# EPS.net
KiCad netlist of a schematic drawn in EAGLE
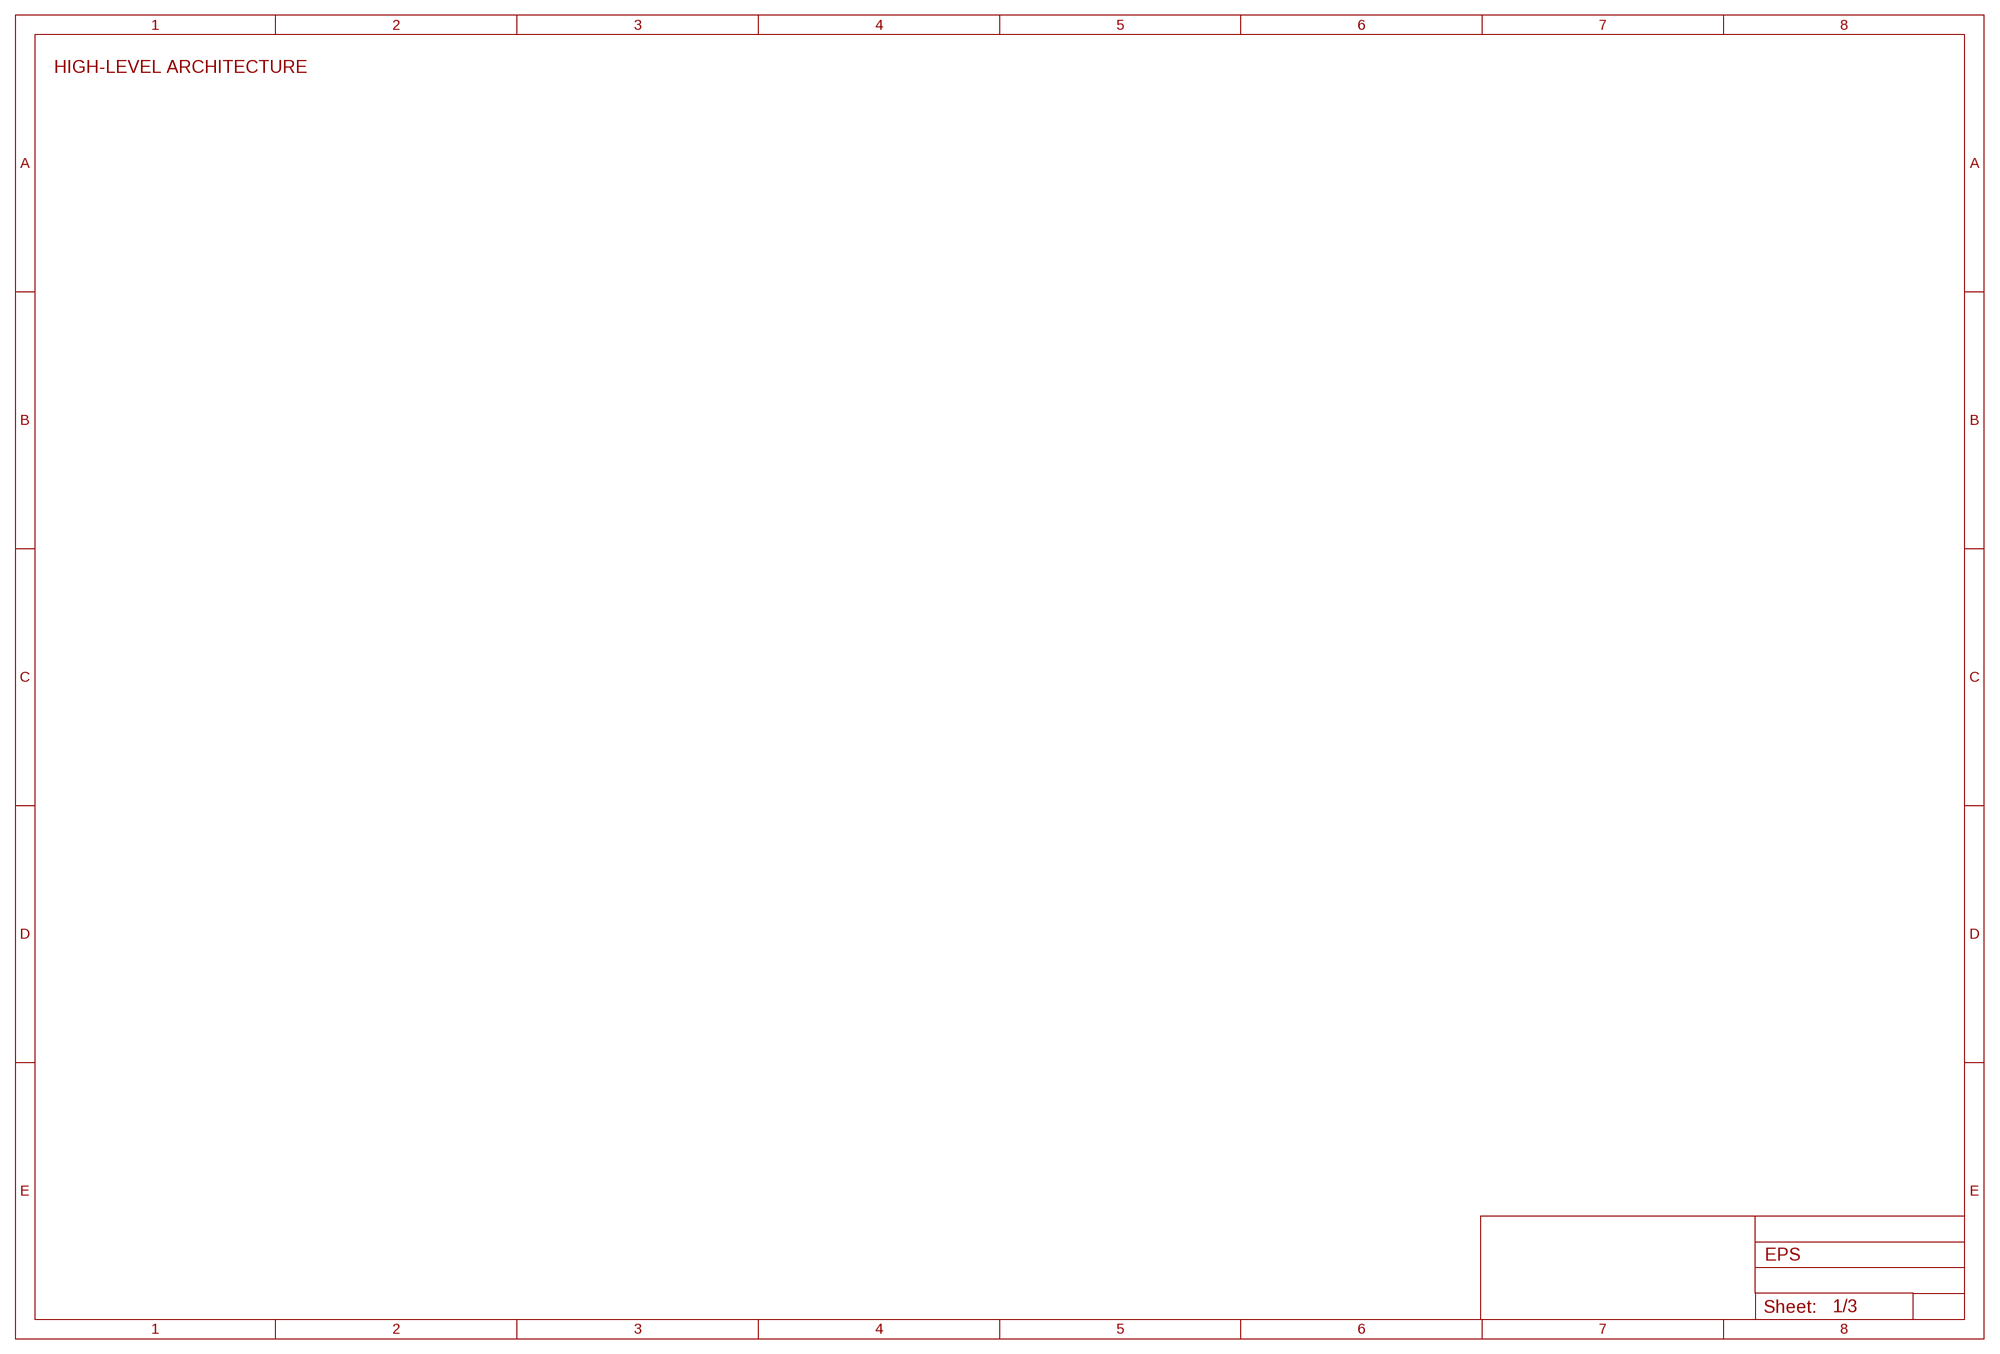
[diagram p0: schematic, sheet 1]
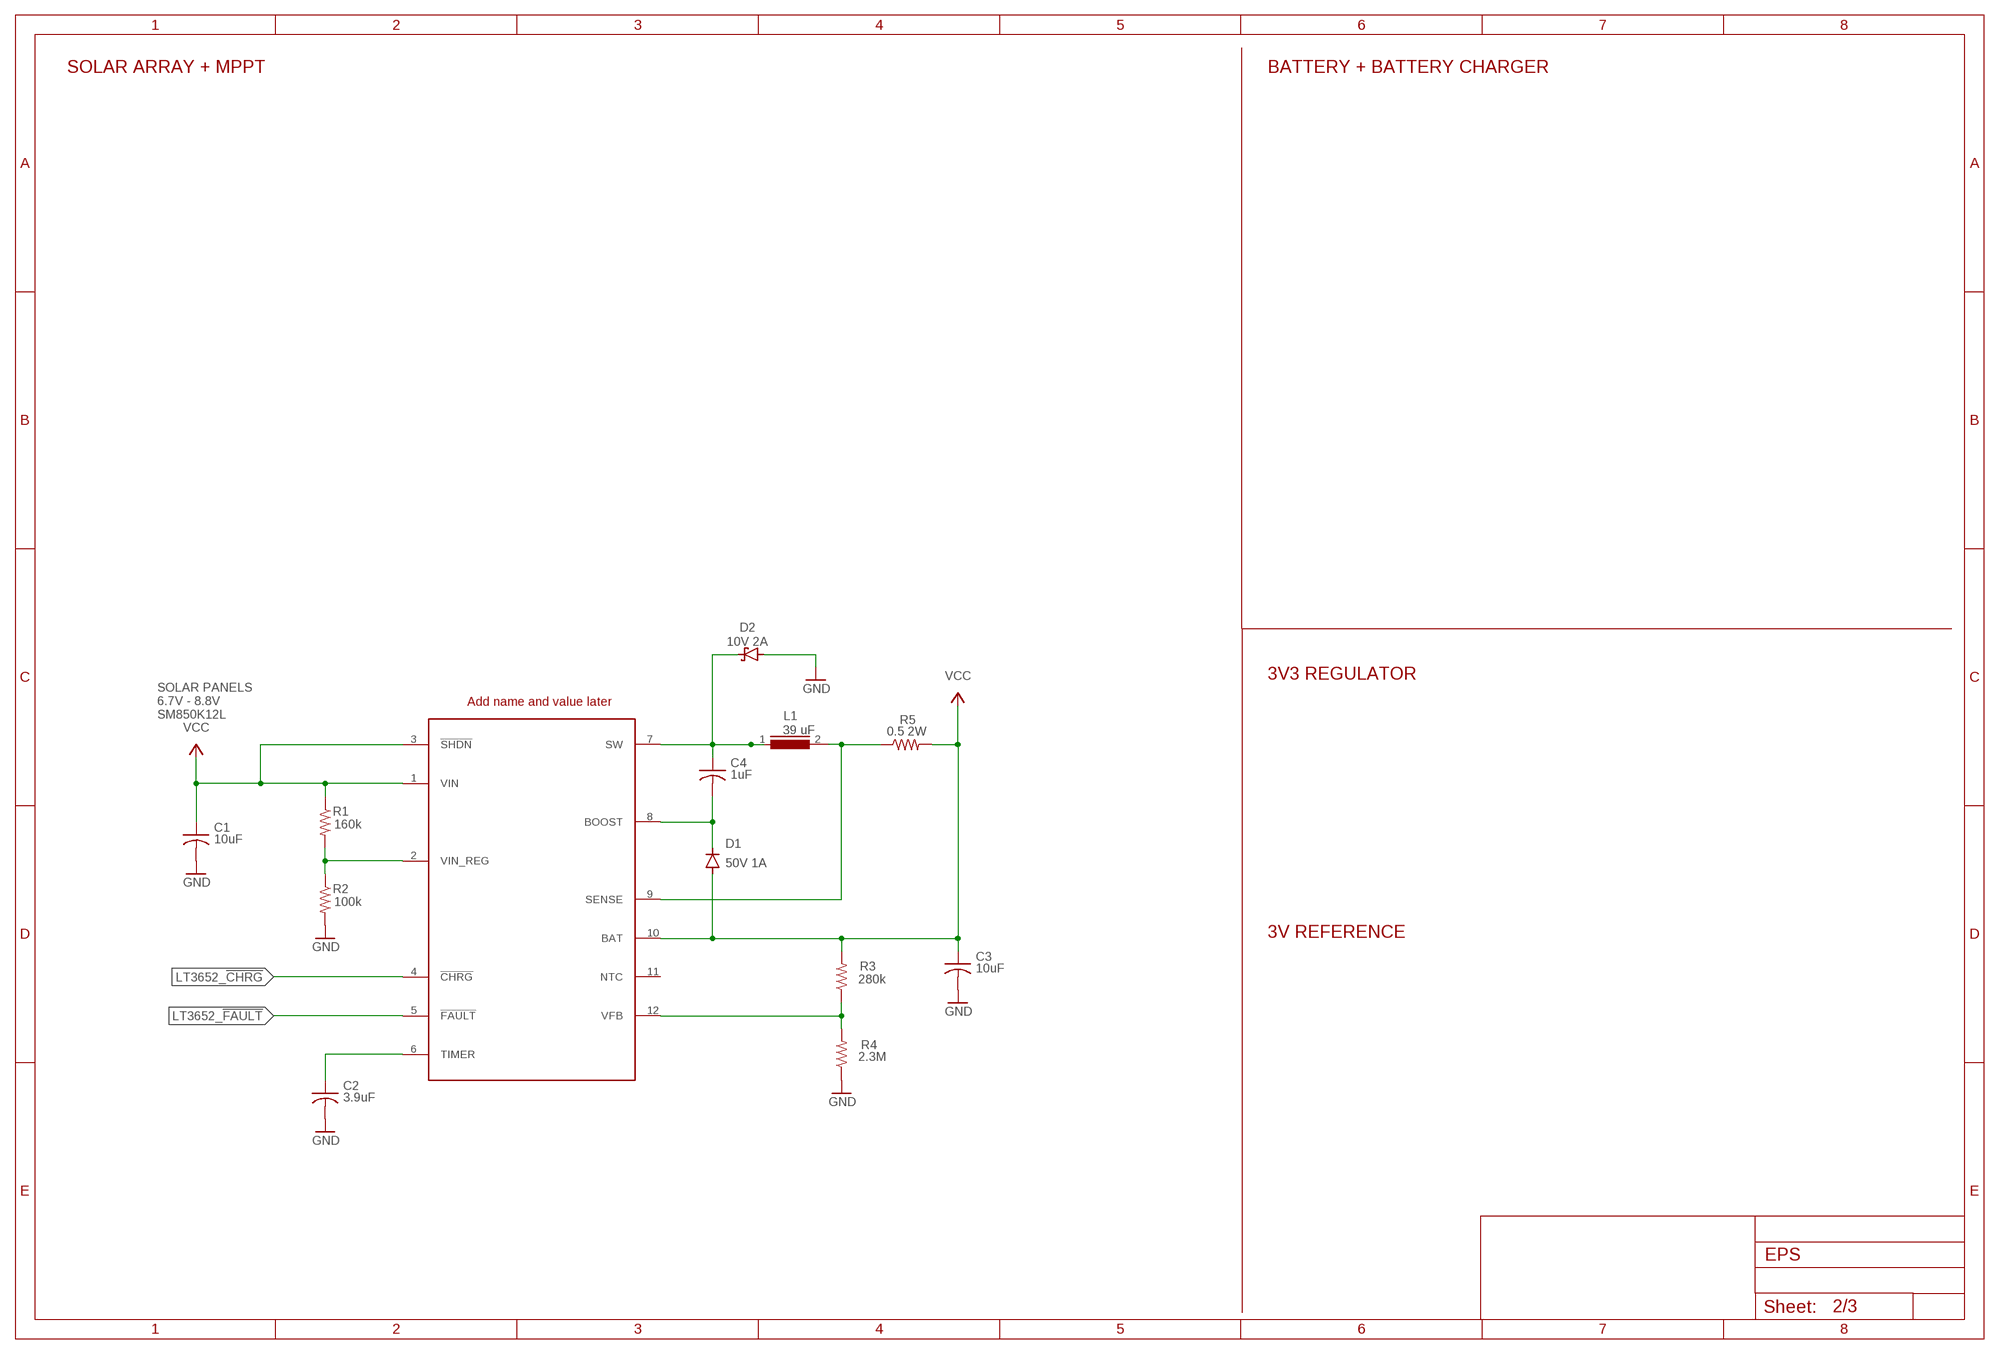
[diagram p1: schematic, sheet 2]
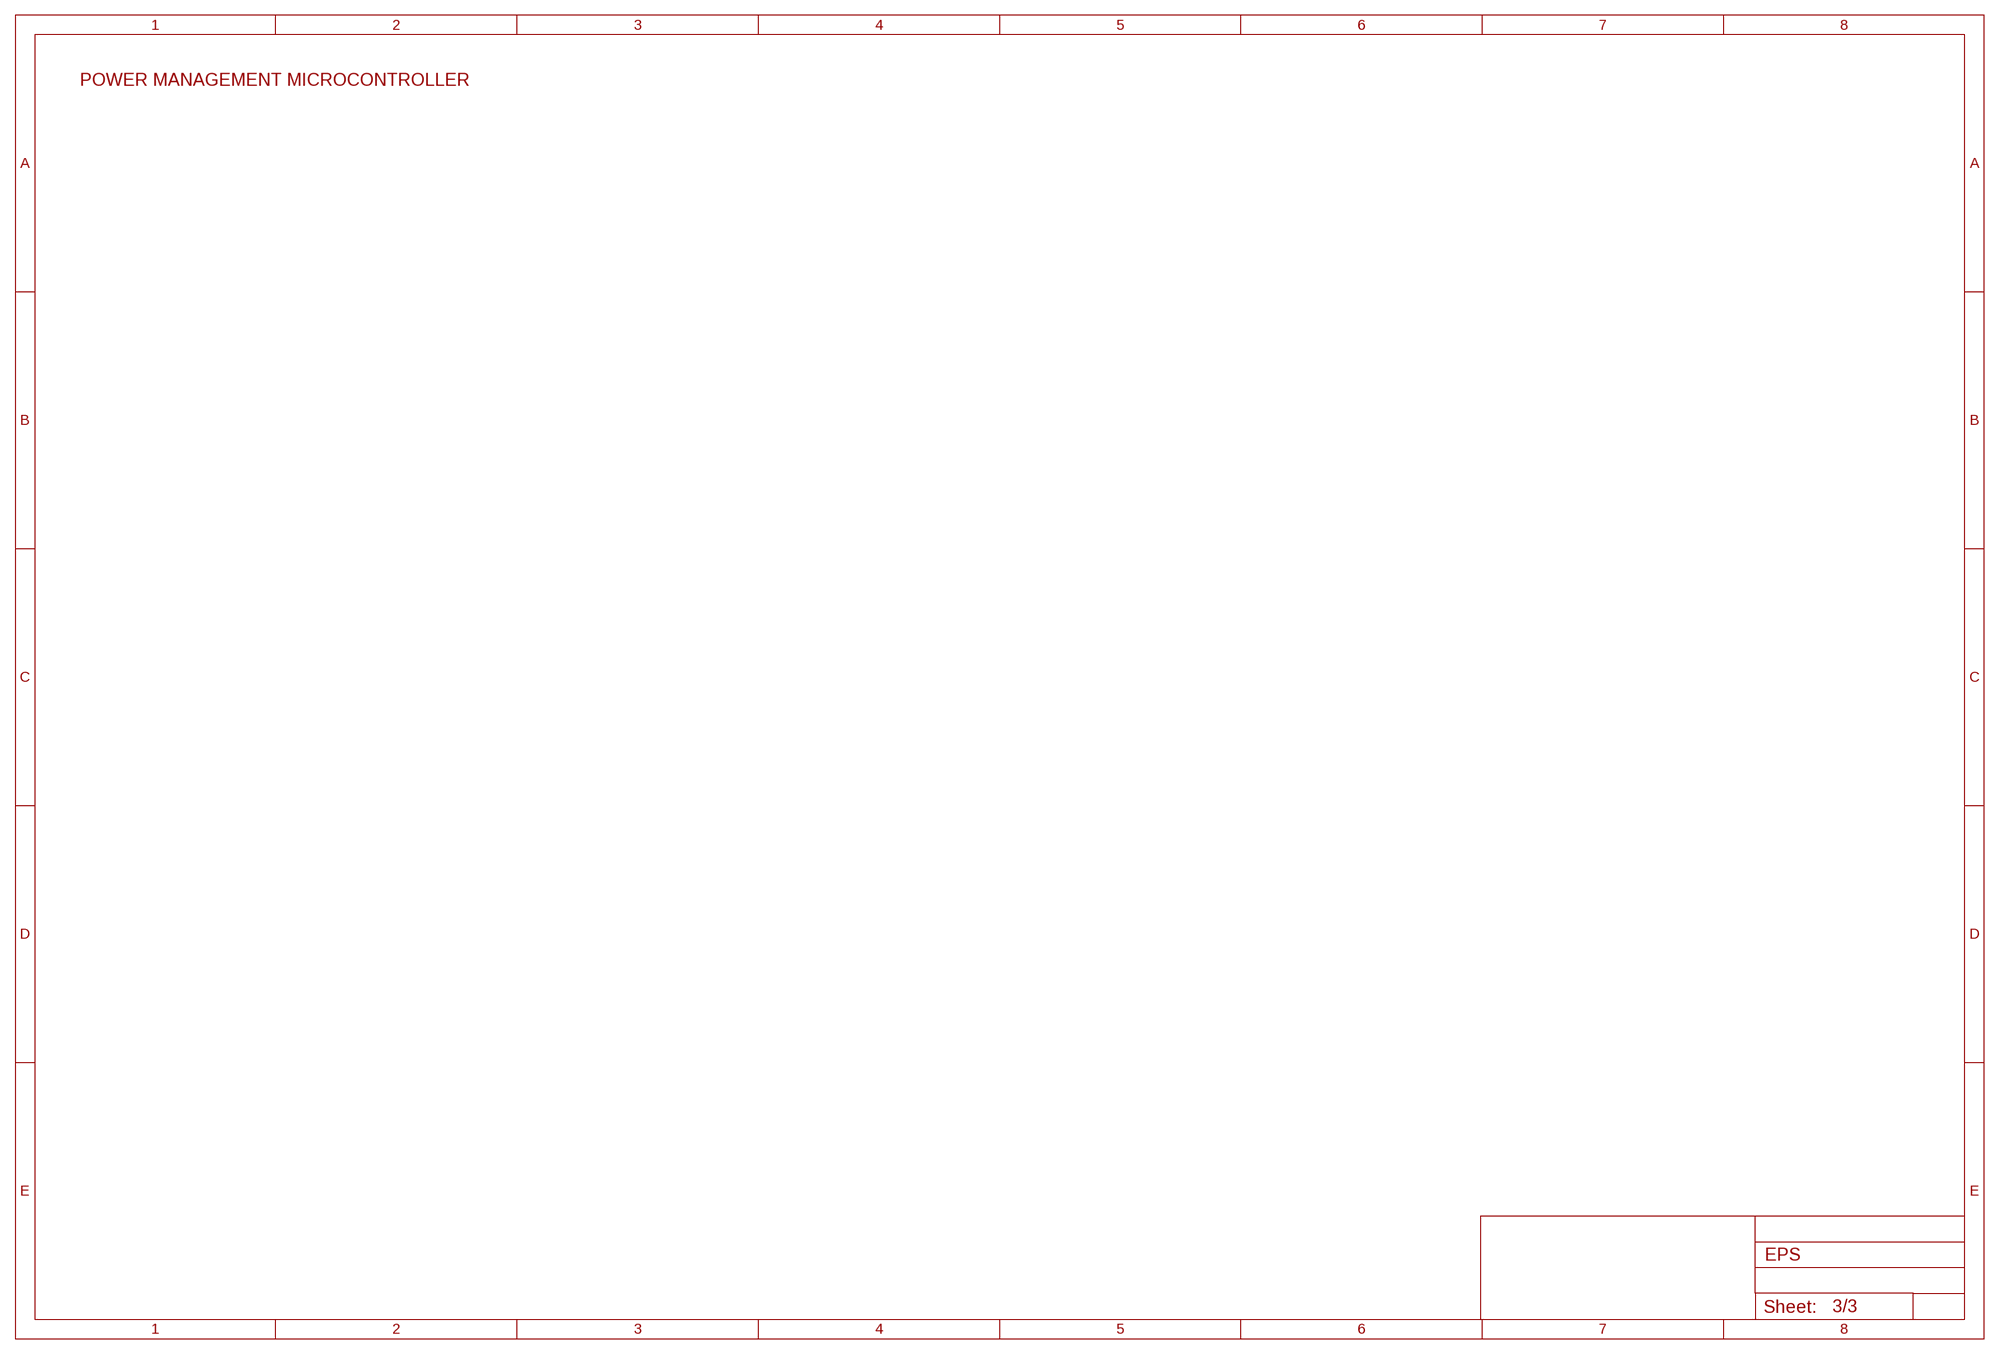
[diagram p2: schematic, sheet 3]

(export (version "E")
  (design (tool "Eeschema 10.0.6"))
  (components
    (comp (ref "C1")
      (value "10uF")
      (footprint "eagle-import:C0603")
      (libsource (lib "eagle-import") (part "C-USC0603"))
    )
    (comp (ref "C2")
      (value "3.9uF")
      (footprint "eagle-import:C0603")
      (libsource (lib "eagle-import") (part "C-USC0603"))
    )
    (comp (ref "C3")
      (value "10uF")
      (footprint "eagle-import:C0603")
      (libsource (lib "eagle-import") (part "C-USC0603"))
    )
    (comp (ref "C4")
      (value "1uF")
      (footprint "eagle-import:C0603")
      (libsource (lib "eagle-import") (part "C-USC0603"))
    )
    (comp (ref "D1")
      (value "50V 1A")
      (footprint "eagle-import:SMA-DO214AC")
      (libsource (lib "eagle-import") (part "GF1"))
    )
    (comp (ref "D2")
      (value "10V 2A")
      (footprint "eagle-import:SOD323_ST")
      (libsource (lib "eagle-import") (part "BAT60J"))
    )
    (comp (ref "L1")
      (value "39 uF")
      (footprint "eagle-import:SUKW2-22")
      (libsource (lib "eagle-import") (part "B82132"))
    )
    (comp (ref "R1")
      (value "160k")
      (footprint "eagle-import:R0603")
      (libsource (lib "eagle-import") (part "R-US_R0603"))
    )
    (comp (ref "R2")
      (value "100k")
      (footprint "eagle-import:R0603")
      (libsource (lib "eagle-import") (part "R-US_R0603"))
    )
    (comp (ref "R3")
      (value "280k")
      (footprint "eagle-import:R0603")
      (libsource (lib "eagle-import") (part "R-US_R0603"))
    )
    (comp (ref "R4")
      (value "2.3M")
      (footprint "eagle-import:R0603")
      (libsource (lib "eagle-import") (part "R-US_R0603"))
    )
    (comp (ref "R5")
      (value "0.5 2W")
      (footprint "eagle-import:R2512W")
      (libsource (lib "eagle-import") (part "R-US_R2512W"))
    )
    (comp (ref "U$1")
      (value "LT3652")
      (footprint "eagle-import:LT3652")
      (fields
        (field (name "DISTPART") "505-LT3652IMSE#PBF-ND")
        (field (name "MANUFACTURER") "Linear Technology")
        (field (name "MFGPART") "LT3652IMSE#PBF")
      )
      (libsource (lib "eagle-import") (part "LT3652"))
    )
  )
  (nets
    (net (code "1") (name "GND") (class "Default")
      (node (ref "C1") (pin "2") (pinfunction "2_2") (pintype "passive"))
      (node (ref "C2") (pin "2") (pinfunction "2_2") (pintype "passive"))
      (node (ref "C3") (pin "2") (pinfunction "2_2") (pintype "passive"))
      (node (ref "D2") (pin "A") (pinfunction "A_A") (pintype "passive"))
      (node (ref "R2") (pin "2") (pinfunction "2_2") (pintype "passive"))
      (node (ref "R4") (pin "1") (pinfunction "1_1") (pintype "passive"))
    )
    (net (code "2") (name "LT3652_~{CHRG}") (class "Default")
      (node (ref "U$1") (pin "4") (pinfunction "~{CHRG}_4") (pintype "bidirectional"))
    )
    (net (code "3") (name "LT3652_~{FAULT}") (class "Default")
      (node (ref "U$1") (pin "5") (pinfunction "~{FAULT}_5") (pintype "bidirectional"))
    )
    (net (code "4") (name "Net-(D1-C)") (class "Default")
      (node (ref "C4") (pin "2") (pinfunction "2_2") (pintype "passive"))
      (node (ref "D1") (pin "K") (pinfunction "C_K") (pintype "passive"))
      (node (ref "U$1") (pin "8") (pinfunction "BOOST_8") (pintype "bidirectional"))
    )
    (net (code "5") (name "Net-(U$1-SENSE)") (class "Default")
      (node (ref "L1") (pin "2") (pinfunction "2_2") (pintype "passive"))
      (node (ref "R5") (pin "1") (pinfunction "1_1") (pintype "passive"))
      (node (ref "U$1") (pin "9") (pinfunction "SENSE_9") (pintype "bidirectional"))
    )
    (net (code "6") (name "Net-(U$1-SW)") (class "Default")
      (node (ref "C4") (pin "1") (pinfunction "1_1") (pintype "passive"))
      (node (ref "D2") (pin "C") (pinfunction "C_C") (pintype "passive"))
      (node (ref "L1") (pin "1") (pinfunction "1_1") (pintype "passive"))
      (node (ref "U$1") (pin "7") (pinfunction "SW_7") (pintype "bidirectional"))
    )
    (net (code "7") (name "Net-(U$1-TIMER)") (class "Default")
      (node (ref "C2") (pin "1") (pinfunction "1_1") (pintype "passive"))
      (node (ref "U$1") (pin "6") (pinfunction "TIMER_6") (pintype "bidirectional"))
    )
    (net (code "8") (name "Net-(U$1-VFB)") (class "Default")
      (node (ref "R3") (pin "1") (pinfunction "1_1") (pintype "passive"))
      (node (ref "R4") (pin "2") (pinfunction "2_2") (pintype "passive"))
      (node (ref "U$1") (pin "12") (pinfunction "VFB_12") (pintype "bidirectional"))
    )
    (net (code "9") (name "Net-(U$1-VIN_REG)") (class "Default")
      (node (ref "R1") (pin "2") (pinfunction "2_2") (pintype "passive"))
      (node (ref "R2") (pin "1") (pinfunction "1_1") (pintype "passive"))
      (node (ref "U$1") (pin "2") (pinfunction "VIN_REG_2") (pintype "bidirectional"))
    )
    (net (code "10") (name "VCC") (class "Default")
      (node (ref "C1") (pin "1") (pinfunction "1_1") (pintype "passive"))
      (node (ref "C3") (pin "1") (pinfunction "1_1") (pintype "passive"))
      (node (ref "D1") (pin "A") (pinfunction "A_A") (pintype "passive"))
      (node (ref "R1") (pin "1") (pinfunction "1_1") (pintype "passive"))
      (node (ref "R3") (pin "2") (pinfunction "2_2") (pintype "passive"))
      (node (ref "R5") (pin "2") (pinfunction "2_2") (pintype "passive"))
      (node (ref "U$1") (pin "1") (pinfunction "VIN_1") (pintype "bidirectional"))
      (node (ref "U$1") (pin "10") (pinfunction "BAT_10") (pintype "bidirectional"))
      (node (ref "U$1") (pin "3") (pinfunction "~{SHDN}_3") (pintype "bidirectional"))
    )
    (net (code "11") (name "unconnected-(U$1-NTC-Pad11)") (class "Default")
      (node (ref "U$1") (pin "11") (pinfunction "NTC_11") (pintype "bidirectional"))
    )
  )
)
